# 6DOF.net
KiCad netlist of a schematic drawn in EAGLE
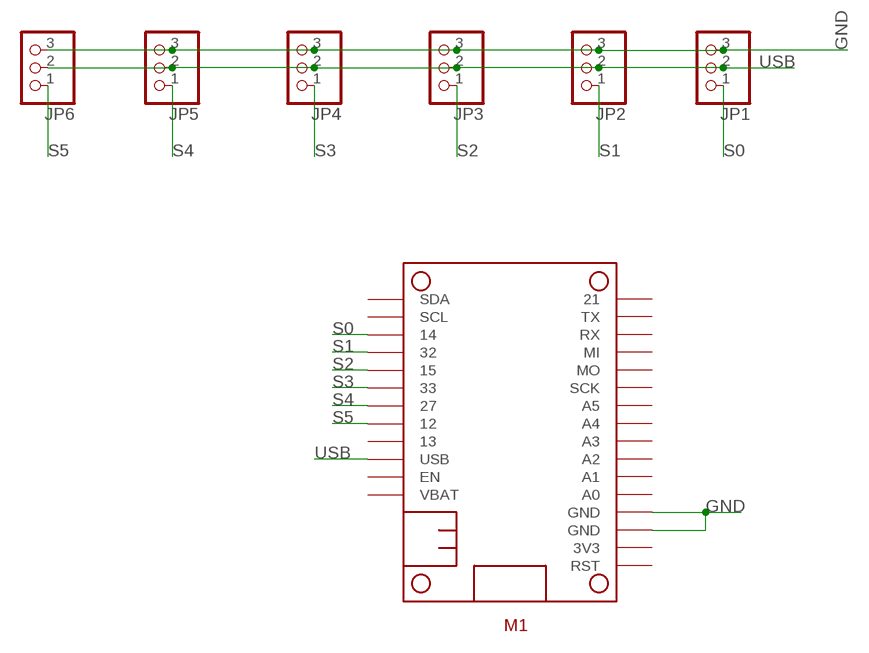
[diagram p0: schematic, sheet 1]

(export (version "E")
  (design (tool "Eeschema 10.0.6"))
  (components
    (comp (ref "JP1")
      (value "PINHD-1X3")
      (footprint "eagle-import:1X03")
      (libsource (lib "eagle-import") (part "PINHD-1X3"))
    )
    (comp (ref "JP2")
      (value "PINHD-1X3")
      (footprint "eagle-import:1X03")
      (libsource (lib "eagle-import") (part "PINHD-1X3"))
    )
    (comp (ref "JP3")
      (value "PINHD-1X3")
      (footprint "eagle-import:1X03")
      (libsource (lib "eagle-import") (part "PINHD-1X3"))
    )
    (comp (ref "JP4")
      (value "PINHD-1X3")
      (footprint "eagle-import:1X03")
      (libsource (lib "eagle-import") (part "PINHD-1X3"))
    )
    (comp (ref "JP5")
      (value "PINHD-1X3")
      (footprint "eagle-import:1X03")
      (libsource (lib "eagle-import") (part "PINHD-1X3"))
    )
    (comp (ref "JP6")
      (value "PINHD-1X3")
      (footprint "eagle-import:1X03")
      (libsource (lib "eagle-import") (part "PINHD-1X3"))
    )
    (comp (ref "M1")
      (value "RARNDT-MISCELANEOUS_FEATHERBOARD_ESP32FETHERWING_DIM_ESP32")
      (footprint "eagle-import:RARNDT-MISCELANEOUS_FEATHERBOARD_ESP32")
      (libsource (lib "eagle-import") (part "RARNDT-MISCELANEOUS_FEATHERBOARD_ESP32FETHERWING_DIM_ESP32"))
    )
  )
  (nets
    (net (code "1") (name "/3V3") (class "Default")
      (node (ref "M1") (pin "2") (pinfunction "3V3_2") (pintype "power_in"))
    )
    (net (code "2") (name "/GND") (class "Default")
      (node (ref "JP1") (pin "3") (pinfunction "3_3") (pintype "passive"))
      (node (ref "JP2") (pin "3") (pinfunction "3_3") (pintype "passive"))
      (node (ref "JP3") (pin "3") (pinfunction "3_3") (pintype "passive"))
      (node (ref "JP4") (pin "3") (pinfunction "3_3") (pintype "passive"))
      (node (ref "JP5") (pin "3") (pinfunction "3_3") (pintype "passive"))
      (node (ref "JP6") (pin "3") (pinfunction "3_3") (pintype "passive"))
      (node (ref "M1") (pin "3") (pinfunction "GND_3") (pintype "passive"))
      (node (ref "M1") (pin "4") (pinfunction "GND_4") (pintype "power_in"))
    )
    (net (code "3") (name "/S0") (class "Default")
      (node (ref "JP1") (pin "1") (pinfunction "1_1") (pintype "passive"))
      (node (ref "M1") (pin "19") (pinfunction "14_19") (pintype "bidirectional"))
    )
    (net (code "4") (name "/S1") (class "Default")
      (node (ref "JP2") (pin "1") (pinfunction "1_1") (pintype "passive"))
      (node (ref "M1") (pin "20") (pinfunction "32_20") (pintype "bidirectional"))
    )
    (net (code "5") (name "/S2") (class "Default")
      (node (ref "JP3") (pin "1") (pinfunction "1_1") (pintype "passive"))
      (node (ref "M1") (pin "21") (pinfunction "15_21") (pintype "bidirectional"))
    )
    (net (code "6") (name "/S3") (class "Default")
      (node (ref "JP4") (pin "1") (pinfunction "1_1") (pintype "passive"))
      (node (ref "M1") (pin "22") (pinfunction "33_22") (pintype "bidirectional"))
    )
    (net (code "7") (name "/S4") (class "Default")
      (node (ref "JP5") (pin "1") (pinfunction "1_1") (pintype "passive"))
      (node (ref "M1") (pin "23") (pinfunction "27_23") (pintype "bidirectional"))
    )
    (net (code "8") (name "/S5") (class "Default")
      (node (ref "JP6") (pin "1") (pinfunction "1_1") (pintype "passive"))
      (node (ref "M1") (pin "24") (pinfunction "12_24") (pintype "bidirectional"))
    )
    (net (code "9") (name "/USB") (class "Default")
      (node (ref "JP1") (pin "2") (pinfunction "2_2") (pintype "passive"))
      (node (ref "JP2") (pin "2") (pinfunction "2_2") (pintype "passive"))
      (node (ref "JP3") (pin "2") (pinfunction "2_2") (pintype "passive"))
      (node (ref "JP4") (pin "2") (pinfunction "2_2") (pintype "passive"))
      (node (ref "JP5") (pin "2") (pinfunction "2_2") (pintype "passive"))
      (node (ref "JP6") (pin "2") (pinfunction "2_2") (pintype "passive"))
      (node (ref "M1") (pin "26") (pinfunction "USB_26") (pintype "power_in"))
    )
    (net (code "10") (name "/VBAT") (class "Default")
      (node (ref "M1") (pin "28") (pinfunction "VBAT_28") (pintype "power_in"))
    )
    (net (code "11") (name "unconnected-(M1-13-Pad25)") (class "Default")
      (node (ref "M1") (pin "25") (pinfunction "13_25") (pintype "bidirectional"))
    )
    (net (code "12") (name "unconnected-(M1-21-Pad16)") (class "Default")
      (node (ref "M1") (pin "16") (pinfunction "21_16") (pintype "passive"))
    )
    (net (code "13") (name "unconnected-(M1-A0-Pad5)") (class "Default")
      (node (ref "M1") (pin "5") (pinfunction "A0_5") (pintype "bidirectional"))
    )
    (net (code "14") (name "unconnected-(M1-A1-Pad6)") (class "Default")
      (node (ref "M1") (pin "6") (pinfunction "A1_6") (pintype "bidirectional"))
    )
    (net (code "15") (name "unconnected-(M1-A2-Pad7)") (class "Default")
      (node (ref "M1") (pin "7") (pinfunction "A2_7") (pintype "bidirectional"))
    )
    (net (code "16") (name "unconnected-(M1-A3-Pad8)") (class "Default")
      (node (ref "M1") (pin "8") (pinfunction "A3_8") (pintype "bidirectional"))
    )
    (net (code "17") (name "unconnected-(M1-A4-Pad9)") (class "Default")
      (node (ref "M1") (pin "9") (pinfunction "A4_9") (pintype "bidirectional"))
    )
    (net (code "18") (name "unconnected-(M1-A5-Pad10)") (class "Default")
      (node (ref "M1") (pin "10") (pinfunction "A5_10") (pintype "bidirectional"))
    )
    (net (code "19") (name "unconnected-(M1-EN-Pad27)") (class "Default")
      (node (ref "M1") (pin "27") (pinfunction "EN_27") (pintype "passive"))
    )
    (net (code "20") (name "unconnected-(M1-MI-Pad13)") (class "Default")
      (node (ref "M1") (pin "13") (pinfunction "MI_13") (pintype "bidirectional"))
    )
    (net (code "21") (name "unconnected-(M1-MO-Pad12)") (class "Default")
      (node (ref "M1") (pin "12") (pinfunction "MO_12") (pintype "bidirectional"))
    )
    (net (code "22") (name "unconnected-(M1-RST-Pad1)") (class "Default")
      (node (ref "M1") (pin "1") (pinfunction "RST_1") (pintype "input"))
    )
    (net (code "23") (name "unconnected-(M1-RX-Pad14)") (class "Default")
      (node (ref "M1") (pin "14") (pinfunction "RX_14") (pintype "bidirectional"))
    )
    (net (code "24") (name "unconnected-(M1-SCK-Pad11)") (class "Default")
      (node (ref "M1") (pin "11") (pinfunction "SCK_11") (pintype "bidirectional"))
    )
    (net (code "25") (name "unconnected-(M1-SCL-Pad18)") (class "Default")
      (node (ref "M1") (pin "18") (pinfunction "SCL_18") (pintype "bidirectional"))
    )
    (net (code "26") (name "unconnected-(M1-SDA-Pad17)") (class "Default")
      (node (ref "M1") (pin "17") (pinfunction "SDA_17") (pintype "bidirectional"))
    )
    (net (code "27") (name "unconnected-(M1-TX-Pad15)") (class "Default")
      (node (ref "M1") (pin "15") (pinfunction "TX_15") (pintype "bidirectional"))
    )
  )
)
